# Micro_USB_Lipo_Charger.net
KiCad netlist of a schematic drawn in EAGLE
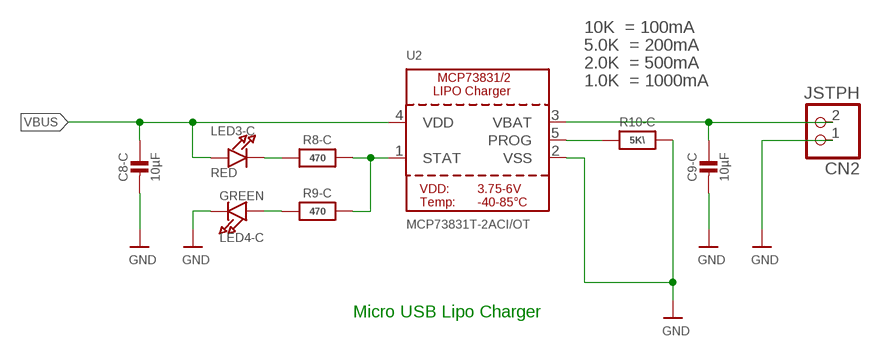
[diagram p0: schematic, sheet 1]

(export (version "E")
  (design (tool "Eeschema 10.0.6"))
  (components
    (comp (ref "C8-C")
      (value "10µF")
      (footprint "eagle-import:0805-NO")
      (libsource (lib "eagle-import") (part "CAP_CERAMIC0805-NOOUTLINE"))
    )
    (comp (ref "C9-C")
      (value "10µF")
      (footprint "eagle-import:0805-NO")
      (libsource (lib "eagle-import") (part "CAP_CERAMIC0805-NOOUTLINE"))
    )
    (comp (ref "CN2")
      (value "JSTPH")
      (footprint "eagle-import:JSTPH2")
      (libsource (lib "eagle-import") (part "JST_2PIN"))
    )
    (comp (ref "LED3-C")
      (value "RED")
      (footprint "eagle-import:CHIPLED_0805_NOOUTLINE")
      (libsource (lib "eagle-import") (part "LED0805_NOOUTLINE"))
    )
    (comp (ref "LED4-C")
      (value "GREEN")
      (footprint "eagle-import:CHIPLED_0805_NOOUTLINE")
      (libsource (lib "eagle-import") (part "LED0805_NOOUTLINE"))
    )
    (comp (ref "R8-C")
      (value "470")
      (footprint "eagle-import:0805-NO")
      (libsource (lib "eagle-import") (part "RESISTOR0805_NOOUTLINE"))
    )
    (comp (ref "R9-C")
      (value "470")
      (footprint "eagle-import:0805-NO")
      (libsource (lib "eagle-import") (part "RESISTOR0805_NOOUTLINE"))
    )
    (comp (ref "R10-C")
      (value "5K\\")
      (footprint "eagle-import:0805-NO")
      (libsource (lib "eagle-import") (part "RESISTOR0805_NOOUTLINE"))
    )
    (comp (ref "U2")
      (value "MCP73831T-2ACI/OT")
      (footprint "eagle-import:SOT23-5")
      (libsource (lib "eagle-import") (part "MCP73831/2"))
    )
  )
  (nets
    (net (code "1") (name "GND") (class "Default")
      (node (ref "C8-C") (pin "2") (pinfunction "2_2") (pintype "passive"))
      (node (ref "C9-C") (pin "2") (pinfunction "2_2") (pintype "passive"))
      (node (ref "CN2") (pin "1") (pinfunction "1_1") (pintype "passive"))
      (node (ref "LED4-C") (pin "C") (pinfunction "C_C") (pintype "passive"))
      (node (ref "R10-C") (pin "2") (pinfunction "2_2") (pintype "passive"))
      (node (ref "U2") (pin "2") (pinfunction "VSS_2") (pintype "power_in"))
    )
    (net (code "2") (name "Net-(LED3-C-PadC)") (class "Default")
      (node (ref "LED3-C") (pin "C") (pinfunction "C_C") (pintype "passive"))
      (node (ref "R8-C") (pin "1") (pinfunction "1_1") (pintype "passive"))
    )
    (net (code "3") (name "Net-(LED4-C-PadA)") (class "Default")
      (node (ref "LED4-C") (pin "A") (pinfunction "A_A") (pintype "passive"))
      (node (ref "R9-C") (pin "1") (pinfunction "1_1") (pintype "passive"))
    )
    (net (code "4") (name "Net-(U2-PROG)") (class "Default")
      (node (ref "R10-C") (pin "1") (pinfunction "1_1") (pintype "passive"))
      (node (ref "U2") (pin "5") (pinfunction "PROG_5") (pintype "input"))
    )
    (net (code "5") (name "Net-(U2-STAT)") (class "Default")
      (node (ref "R8-C") (pin "2") (pinfunction "2_2") (pintype "passive"))
      (node (ref "R9-C") (pin "2") (pinfunction "2_2") (pintype "passive"))
      (node (ref "U2") (pin "1") (pinfunction "STAT_1") (pintype "output"))
    )
    (net (code "6") (name "Net-(U2-VBAT)") (class "Default")
      (node (ref "C9-C") (pin "1") (pinfunction "1_1") (pintype "passive"))
      (node (ref "CN2") (pin "2") (pinfunction "2_2") (pintype "passive"))
      (node (ref "U2") (pin "3") (pinfunction "VBAT_3") (pintype "power_in"))
    )
    (net (code "7") (name "VBUS") (class "Default")
      (node (ref "C8-C") (pin "1") (pinfunction "1_1") (pintype "passive"))
      (node (ref "LED3-C") (pin "A") (pinfunction "A_A") (pintype "passive"))
      (node (ref "U2") (pin "4") (pinfunction "VDD_4") (pintype "power_in"))
    )
  )
)
